# v1_5_Power.net
KiCad netlist of a schematic drawn in Altium Designer
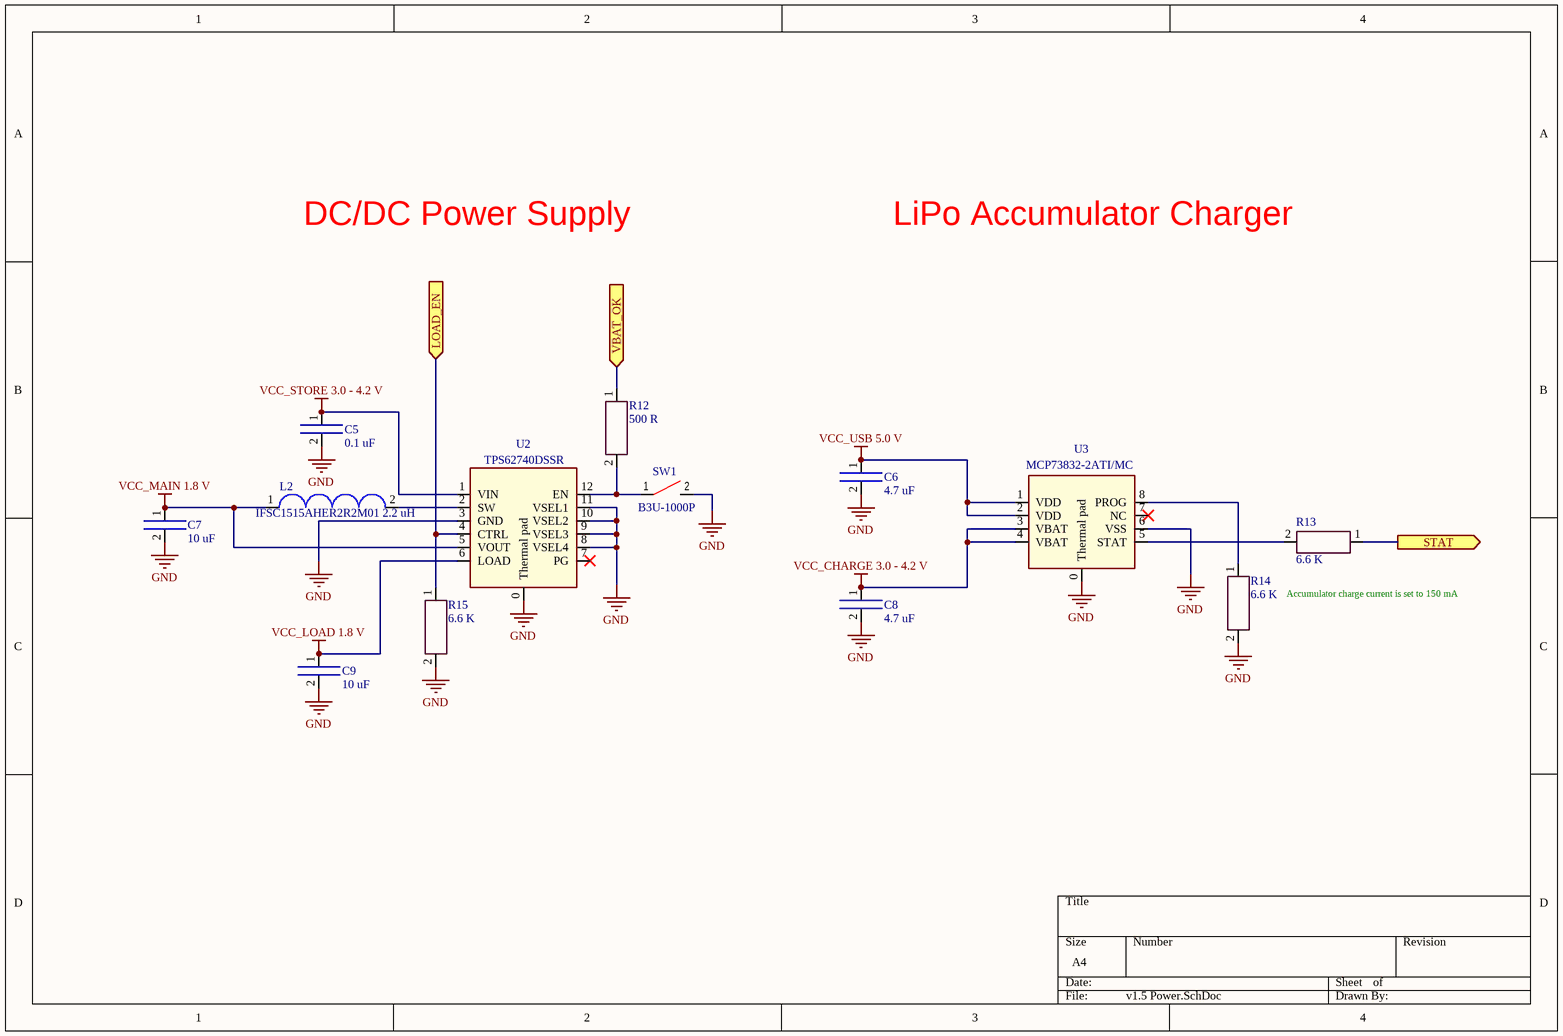
[diagram p0: v1.5 Power.SchDoc]

(export (version "E")
  (design (tool "Eeschema 10.0.6"))
  (components
    (comp (ref "C5")
      (value "0.1 uF")
      (footprint "Ungravity Library:0402")
      (libsource (lib "Ungravity Library") (part "Capasistor"))
    )
    (comp (ref "C6")
      (value "4.7 uF")
      (footprint "Ungravity Library:0402")
      (libsource (lib "Ungravity Library") (part "Capasistor"))
    )
    (comp (ref "C7")
      (value "10 uF")
      (footprint "Ungravity Library:0603")
      (libsource (lib "Ungravity Library") (part "Capasistor"))
    )
    (comp (ref "C8")
      (value "4.7 uF")
      (footprint "Ungravity Library:0402")
      (libsource (lib "Ungravity Library") (part "Capasistor"))
    )
    (comp (ref "C9")
      (value "10 uF")
      (footprint "Ungravity Library:0603")
      (libsource (lib "Ungravity Library") (part "Capasistor"))
    )
    (comp (ref "L2")
      (value "IFSC1515AHER2R2M01 2.2 uH")
      (footprint "Ungravity Library:IFSC1515-AH-01")
      (libsource (lib "Ungravity Library") (part "Inductor"))
    )
    (comp (ref "R12")
      (value "500 R")
      (footprint "Ungravity Library:0402")
      (libsource (lib "Ungravity Library") (part "Resistor"))
    )
    (comp (ref "R13")
      (value "6.6 K")
      (footprint "Ungravity Library:0402")
      (libsource (lib "Ungravity Library") (part "Resistor"))
    )
    (comp (ref "R14")
      (value "6.6 K")
      (footprint "Ungravity Library:0402")
      (libsource (lib "Ungravity Library") (part "Resistor"))
    )
    (comp (ref "R15")
      (value "6.6 K")
      (footprint "Ungravity Library:0402")
      (libsource (lib "Ungravity Library") (part "Resistor"))
    )
    (comp (ref "SW1")
      (value "B3U-1000P")
      (footprint "Ungravity Library:B3U-1000P")
      (libsource (lib "Ungravity Library") (part "Tact switch"))
    )
    (comp (ref "U2")
      (value "TPS62740DSSR")
      (footprint "Ungravity Library:TPS62740")
      (libsource (lib "Ungravity Library") (part "TPS62740"))
    )
    (comp (ref "U3")
      (value "MCP73832-2ATI/MC")
      (footprint "Ungravity Library:MCP73832-2ATI/MC")
      (libsource (lib "Ungravity Library") (part "MCP73832-2ATI/MC"))
    )
  )
  (nets
    (net (code "1") (name "/LOAD_EN") (class "Default")
      (node (ref "R15") (pin "1") (pinfunction "1_1") (pintype "passive"))
      (node (ref "U2") (pin "4") (pinfunction "CTRL_4") (pintype "passive"))
    )
    (net (code "2") (name "/STAT") (class "Default")
      (node (ref "R13") (pin "1") (pinfunction "1_1") (pintype "passive"))
    )
    (net (code "3") (name "/VBAT_OK") (class "Default")
      (node (ref "R12") (pin "1") (pinfunction "1_1") (pintype "passive"))
    )
    (net (code "4") (name "GND") (class "Default")
      (node (ref "C5") (pin "2") (pinfunction "2_2") (pintype "passive"))
      (node (ref "C6") (pin "2") (pinfunction "2_2") (pintype "passive"))
      (node (ref "C7") (pin "2") (pinfunction "2_2") (pintype "passive"))
      (node (ref "C8") (pin "2") (pinfunction "2_2") (pintype "passive"))
      (node (ref "C9") (pin "2") (pinfunction "2_2") (pintype "passive"))
      (node (ref "R14") (pin "2") (pinfunction "2_2") (pintype "passive"))
      (node (ref "R15") (pin "2") (pinfunction "2_2") (pintype "passive"))
      (node (ref "SW1") (pin "2") (pinfunction "2_2") (pintype "passive"))
      (node (ref "U2") (pin "0") (pinfunction "Thermal_pad_0") (pintype "passive"))
      (node (ref "U2") (pin "10") (pinfunction "VSEL2_10") (pintype "passive"))
      (node (ref "U2") (pin "11") (pinfunction "VSEL1_11") (pintype "passive"))
      (node (ref "U2") (pin "3") (pinfunction "GND_3") (pintype "passive"))
      (node (ref "U2") (pin "8") (pinfunction "VSEL4_8") (pintype "passive"))
      (node (ref "U2") (pin "9") (pinfunction "VSEL3_9") (pintype "passive"))
      (node (ref "U3") (pin "0") (pinfunction "Thermal_pad_0") (pintype "passive"))
      (node (ref "U3") (pin "6") (pinfunction "VSS_6") (pintype "passive"))
    )
    (net (code "5") (name "Net-(U2-EN)") (class "Default")
      (node (ref "R12") (pin "2") (pinfunction "2_2") (pintype "passive"))
      (node (ref "SW1") (pin "1") (pinfunction "1_1") (pintype "passive"))
      (node (ref "U2") (pin "12") (pinfunction "EN_12") (pintype "passive"))
    )
    (net (code "6") (name "Net-(U2-SW)") (class "Default")
      (node (ref "L2") (pin "2") (pinfunction "2_2") (pintype "passive"))
      (node (ref "U2") (pin "2") (pinfunction "SW_2") (pintype "passive"))
    )
    (net (code "7") (name "Net-(U3-PROG)") (class "Default")
      (node (ref "R14") (pin "1") (pinfunction "1_1") (pintype "passive"))
      (node (ref "U3") (pin "8") (pinfunction "PROG_8") (pintype "passive"))
    )
    (net (code "8") (name "Net-(U3-STAT)") (class "Default")
      (node (ref "R13") (pin "2") (pinfunction "2_2") (pintype "passive"))
      (node (ref "U3") (pin "5") (pinfunction "STAT_5") (pintype "passive"))
    )
    (net (code "9") (name "VCC_CHARGE 3.0 - 4.2 V") (class "Default")
      (node (ref "C8") (pin "1") (pinfunction "1_1") (pintype "passive"))
      (node (ref "U3") (pin "3") (pinfunction "VBAT_3") (pintype "passive"))
      (node (ref "U3") (pin "4") (pinfunction "VBAT_4") (pintype "passive"))
    )
    (net (code "10") (name "VCC_LOAD 1.8 V") (class "Default")
      (node (ref "C9") (pin "1") (pinfunction "1_1") (pintype "passive"))
      (node (ref "U2") (pin "6") (pinfunction "LOAD_6") (pintype "passive"))
    )
    (net (code "11") (name "VCC_MAIN 1.8 V") (class "Default")
      (node (ref "C7") (pin "1") (pinfunction "1_1") (pintype "passive"))
      (node (ref "L2") (pin "1") (pinfunction "1_1") (pintype "passive"))
      (node (ref "U2") (pin "5") (pinfunction "VOUT_5") (pintype "passive"))
    )
    (net (code "12") (name "VCC_STORE 3.0 - 4.2 V") (class "Default")
      (node (ref "C5") (pin "1") (pinfunction "1_1") (pintype "passive"))
      (node (ref "U2") (pin "1") (pinfunction "VIN_1") (pintype "passive"))
    )
    (net (code "13") (name "VCC_USB 5.0 V") (class "Default")
      (node (ref "C6") (pin "1") (pinfunction "1_1") (pintype "passive"))
      (node (ref "U3") (pin "1") (pinfunction "VDD_1") (pintype "passive"))
      (node (ref "U3") (pin "2") (pinfunction "VDD_2") (pintype "passive"))
    )
    (net (code "14") (name "unconnected-(U2-PG-Pad7)") (class "Default")
      (node (ref "U2") (pin "7") (pinfunction "PG_7") (pintype "passive+no_connect"))
    )
    (net (code "15") (name "unconnected-(U3-NC-Pad7)") (class "Default")
      (node (ref "U3") (pin "7") (pinfunction "NC_7") (pintype "passive+no_connect"))
    )
  )
)
